# esp-rgbw.net
KiCad netlist of a schematic drawn in EAGLE
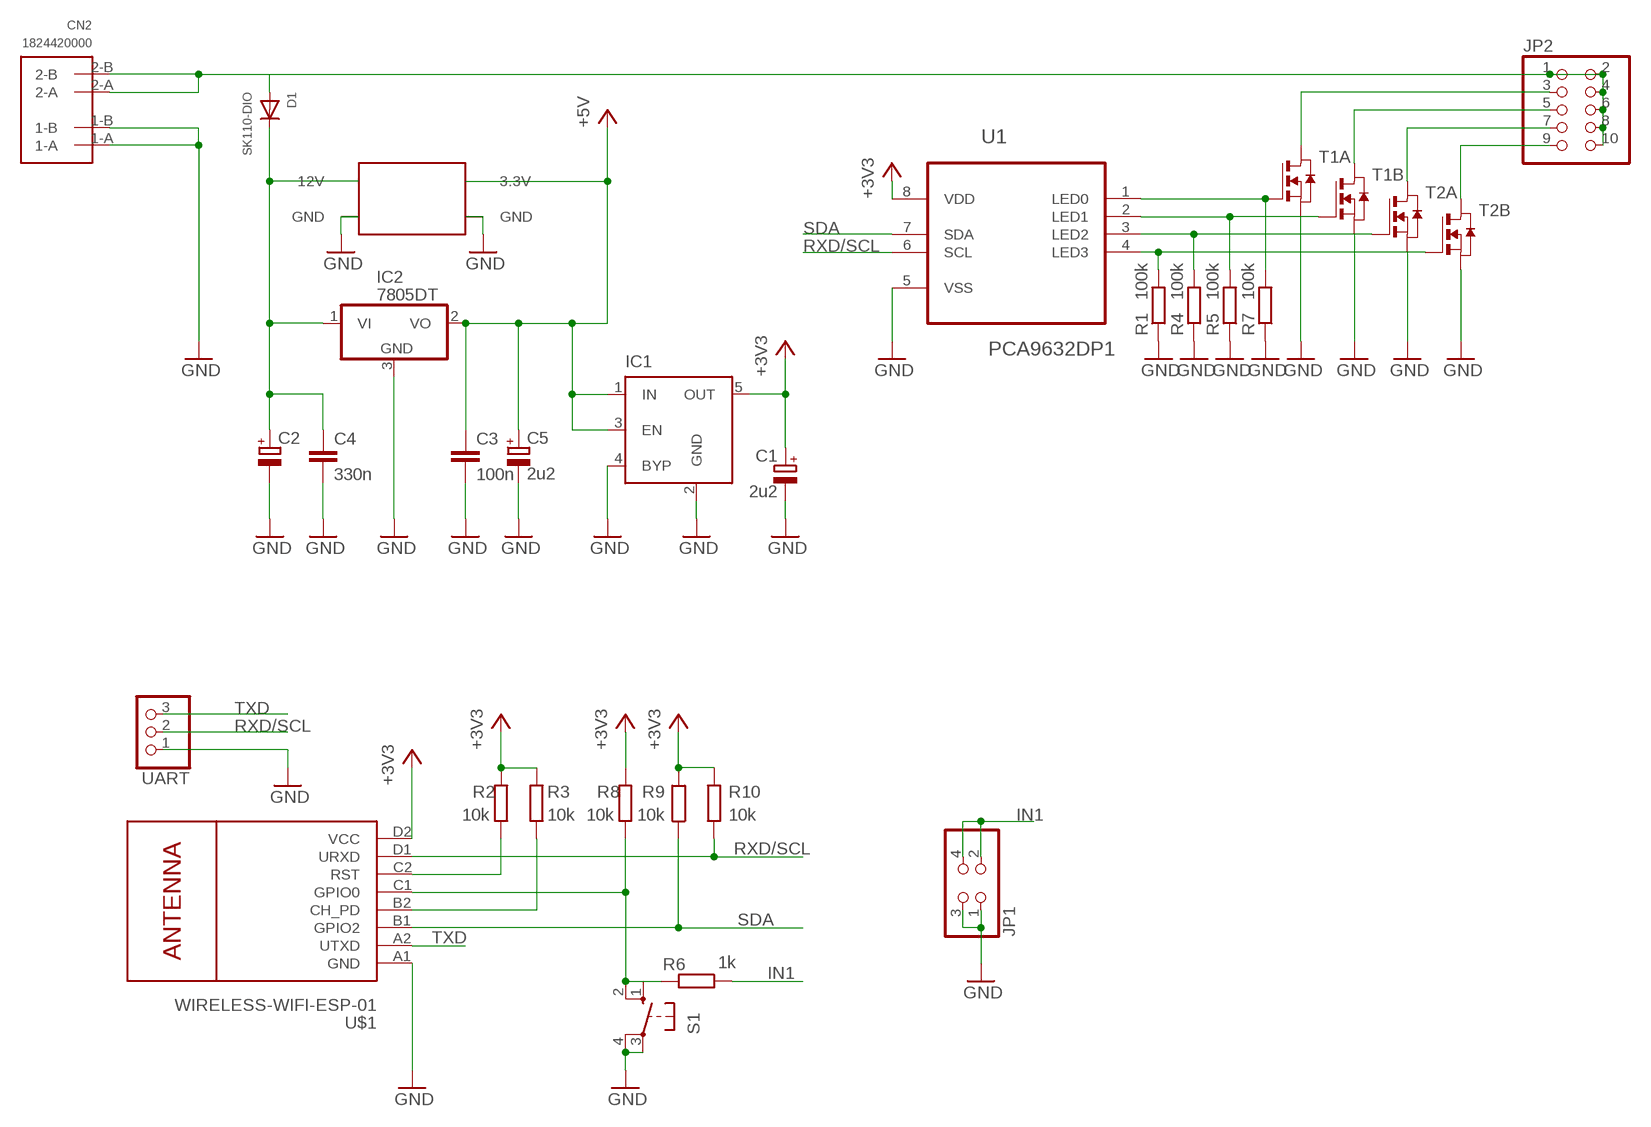
[diagram p0: schematic, sheet 1]

(export (version "E")
  (design (tool "Eeschema 10.0.6"))
  (components
    (comp (ref "C1")
      (value "2u2")
      (footprint "eagle-import:SMC_B")
      (libsource (lib "eagle-import") (part "CPOL-EUSMCB"))
    )
    (comp (ref "C2")
      (value "CPOL-EUC/6032-28R")
      (footprint "eagle-import:C_6032-28R")
      (libsource (lib "eagle-import") (part "CPOL-EUC/6032-28R"))
    )
    (comp (ref "C3")
      (value "100n")
      (footprint "eagle-import:C0805")
      (libsource (lib "eagle-import") (part "C-EUC0805"))
    )
    (comp (ref "C4")
      (value "330n")
      (footprint "eagle-import:C0805")
      (libsource (lib "eagle-import") (part "C-EUC0805"))
    )
    (comp (ref "C5")
      (value "2u2")
      (footprint "eagle-import:SMC_B")
      (libsource (lib "eagle-import") (part "CPOL-EUSMCB"))
    )
    (comp (ref "CN2")
      (value "1824420000")
      (footprint "eagle-import:1824420000")
      (fields (field (name "MF") "Weidmuller"))
      (libsource (lib "eagle-import") (part "1824420000"))
    )
    (comp (ref "D1")
      (value "SK110-DIO")
      (footprint "eagle-import:SMADIODE")
      (libsource (lib "eagle-import") (part "DIODESMA"))
    )
    (comp (ref "IC1")
      (value "MIC5219XX")
      (footprint "eagle-import:SOT23-5")
      (libsource (lib "eagle-import") (part "MIC5219XX"))
    )
    (comp (ref "IC2")
      (value "7805DT")
      (footprint "eagle-import:TO252")
      (libsource (lib "eagle-import") (part "78DT05"))
    )
    (comp (ref "JP1")
      (value "PINHD-2X2")
      (footprint "eagle-import:2X02")
      (libsource (lib "eagle-import") (part "PINHD-2X2"))
    )
    (comp (ref "JP2")
      (value "PINHD-2X5")
      (footprint "eagle-import:2X05")
      (libsource (lib "eagle-import") (part "PINHD-2X5"))
    )
    (comp (ref "R1")
      (value "100k")
      (footprint "eagle-import:R0805")
      (libsource (lib "eagle-import") (part "R-EU_R0805"))
    )
    (comp (ref "R2")
      (value "10k")
      (footprint "eagle-import:R0805")
      (libsource (lib "eagle-import") (part "R-EU_R0805"))
    )
    (comp (ref "R3")
      (value "10k")
      (footprint "eagle-import:R0805")
      (libsource (lib "eagle-import") (part "R-EU_R0805"))
    )
    (comp (ref "R4")
      (value "100k")
      (footprint "eagle-import:R0805")
      (libsource (lib "eagle-import") (part "R-EU_R0805"))
    )
    (comp (ref "R5")
      (value "100k")
      (footprint "eagle-import:R0805")
      (libsource (lib "eagle-import") (part "R-EU_R0805"))
    )
    (comp (ref "R6")
      (value "1k")
      (footprint "eagle-import:R0805")
      (libsource (lib "eagle-import") (part "R-EU_R0805"))
    )
    (comp (ref "R7")
      (value "100k")
      (footprint "eagle-import:R0805")
      (libsource (lib "eagle-import") (part "R-EU_R0805"))
    )
    (comp (ref "R8")
      (value "10k")
      (footprint "eagle-import:R0805")
      (libsource (lib "eagle-import") (part "R-EU_R0805"))
    )
    (comp (ref "R9")
      (value "10k")
      (footprint "eagle-import:R0805")
      (libsource (lib "eagle-import") (part "R-EU_R0805"))
    )
    (comp (ref "R10")
      (value "10k")
      (footprint "eagle-import:R0805")
      (libsource (lib "eagle-import") (part "R-EU_R0805"))
    )
    (comp (ref "S1")
      (value "10-XX")
      (footprint "eagle-import:B3F-10XX")
      (fields (field (name "MPN") "B3F-1000"))
      (libsource (lib "eagle-import") (part "10-XX"))
    )
    (comp (ref "T1")
      (value "NMOS2SO8")
      (footprint "eagle-import:SO8")
      (libsource (lib "eagle-import") (part "NMOS2SO8"))
    )
    (comp (ref "T2")
      (value "NMOS2SO8")
      (footprint "eagle-import:SO8")
      (libsource (lib "eagle-import") (part "NMOS2SO8"))
    )
    (comp (ref "U$1")
      (value "WIRELESS-WIFI-ESP-01")
      (footprint "eagle-import:WIRELESS-WIFI-ESP-01")
      (libsource (lib "eagle-import") (part "WIRELESS-WIFI-ESP-01"))
    )
    (comp (ref "U$2")
      (value "MP2307-MINI-360")
      (footprint "eagle-import:MP2307-MINI-360")
      (libsource (lib "eagle-import") (part "MP2307-MINI-360"))
    )
    (comp (ref "U1")
      (value "PCA9632DP1")
      (footprint "eagle-import:SOP65P490X110-8N")
      (libsource (lib "eagle-import") (part "PCA9632DP1"))
    )
    (comp (ref "UART")
      (value "PINHD-1X3")
      (footprint "eagle-import:1X03")
      (libsource (lib "eagle-import") (part "PINHD-1X3"))
    )
  )
  (nets
    (net (code "1") (name "+3V3") (class "Default")
      (node (ref "C1") (pin "+") (pinfunction "+_+") (pintype "passive"))
      (node (ref "IC1") (pin "5") (pinfunction "OUT_5") (pintype "output"))
      (node (ref "R10") (pin "2") (pinfunction "2_2") (pintype "passive"))
      (node (ref "R2") (pin "2") (pinfunction "2_2") (pintype "passive"))
      (node (ref "R3") (pin "2") (pinfunction "2_2") (pintype "passive"))
      (node (ref "R8") (pin "2") (pinfunction "2_2") (pintype "passive"))
      (node (ref "R9") (pin "2") (pinfunction "2_2") (pintype "passive"))
      (node (ref "U$1") (pin "D2") (pinfunction "VCC_D2") (pintype "power_in"))
      (node (ref "U1") (pin "8") (pinfunction "VDD_8") (pintype "power_in"))
    )
    (net (code "2") (name "+5V") (class "Default")
      (node (ref "C3") (pin "1") (pinfunction "1_1") (pintype "passive"))
      (node (ref "C5") (pin "+") (pinfunction "+_+") (pintype "passive"))
      (node (ref "IC1") (pin "1") (pinfunction "IN_1") (pintype "input"))
      (node (ref "IC1") (pin "3") (pinfunction "EN_3") (pintype "input"))
      (node (ref "IC2") (pin "2") (pinfunction "VO_2") (pintype "passive"))
      (node (ref "U$2") (pin "3.3V") (pinfunction "3.3V_3.3V") (pintype "power_in"))
    )
    (net (code "3") (name "/IN1") (class "Default")
      (node (ref "JP1") (pin "2") (pinfunction "2_2") (pintype "passive"))
      (node (ref "JP1") (pin "4") (pinfunction "4_4") (pintype "passive"))
      (node (ref "R6") (pin "1") (pinfunction "1_1") (pintype "passive"))
    )
    (net (code "4") (name "/RXD{slash}SCL") (class "Default")
      (node (ref "R10") (pin "1") (pinfunction "1_1") (pintype "passive"))
      (node (ref "U$1") (pin "D1") (pinfunction "URXD_D1") (pintype "bidirectional"))
      (node (ref "U1") (pin "6") (pinfunction "SCL_6") (pintype "input"))
      (node (ref "UART") (pin "2") (pinfunction "2_2") (pintype "passive"))
    )
    (net (code "5") (name "/SDA") (class "Default")
      (node (ref "R9") (pin "1") (pinfunction "1_1") (pintype "passive"))
      (node (ref "U$1") (pin "B1") (pinfunction "GPIO2_B1") (pintype "bidirectional"))
      (node (ref "U1") (pin "7") (pinfunction "SDA_7") (pintype "bidirectional"))
    )
    (net (code "6") (name "/TXD") (class "Default")
      (node (ref "U$1") (pin "A2") (pinfunction "UTXD_A2") (pintype "bidirectional"))
      (node (ref "UART") (pin "3") (pinfunction "3_3") (pintype "passive"))
    )
    (net (code "7") (name "GND") (class "Default")
      (node (ref "C1") (pin "-") (pinfunction "-_-") (pintype "passive"))
      (node (ref "C2") (pin "-") (pinfunction "-_-") (pintype "passive"))
      (node (ref "C3") (pin "2") (pinfunction "2_2") (pintype "passive"))
      (node (ref "C4") (pin "2") (pinfunction "2_2") (pintype "passive"))
      (node (ref "C5") (pin "-") (pinfunction "-_-") (pintype "passive"))
      (node (ref "CN2") (pin "1-A") (pinfunction "1-A_1-A") (pintype "bidirectional"))
      (node (ref "CN2") (pin "1-B") (pinfunction "1-B_1-B") (pintype "bidirectional"))
      (node (ref "IC1") (pin "2") (pinfunction "GND_2") (pintype "power_in"))
      (node (ref "IC1") (pin "4") (pinfunction "BYP_4") (pintype "passive"))
      (node (ref "IC2") (pin "3") (pinfunction "GND_3") (pintype "passive"))
      (node (ref "JP1") (pin "1") (pinfunction "1_1") (pintype "passive"))
      (node (ref "JP1") (pin "3") (pinfunction "3_3") (pintype "passive"))
      (node (ref "R1") (pin "1") (pinfunction "1_1") (pintype "passive"))
      (node (ref "R4") (pin "1") (pinfunction "1_1") (pintype "passive"))
      (node (ref "R5") (pin "1") (pinfunction "1_1") (pintype "passive"))
      (node (ref "R7") (pin "1") (pinfunction "1_1") (pintype "passive"))
      (node (ref "S1") (pin "3") (pinfunction "P_3") (pintype "passive"))
      (node (ref "S1") (pin "4") (pinfunction "P1_4") (pintype "passive"))
      (node (ref "T1") (pin "1") (pinfunction "S_1") (pintype "passive"))
      (node (ref "T1") (pin "3") (pinfunction "S_3") (pintype "passive"))
      (node (ref "T2") (pin "1") (pinfunction "S_1") (pintype "passive"))
      (node (ref "T2") (pin "3") (pinfunction "S_3") (pintype "passive"))
      (node (ref "U$1") (pin "A1") (pinfunction "GND_A1") (pintype "power_in"))
      (node (ref "U$2") (pin "GND@1") (pinfunction "GND_GND@1") (pintype "power_in"))
      (node (ref "U$2") (pin "GND@2") (pinfunction "GND_GND@2") (pintype "power_in"))
      (node (ref "U1") (pin "5") (pinfunction "VSS_5") (pintype "passive"))
      (node (ref "UART") (pin "1") (pinfunction "1_1") (pintype "passive"))
    )
    (net (code "8") (name "Net-(CN2-Pad2-A)") (class "Default")
      (node (ref "CN2") (pin "2-A") (pinfunction "2-A_2-A") (pintype "bidirectional"))
      (node (ref "CN2") (pin "2-B") (pinfunction "2-B_2-B") (pintype "bidirectional"))
      (node (ref "D1") (pin "A") (pinfunction "A_A") (pintype "passive"))
      (node (ref "JP2") (pin "1") (pinfunction "1_1") (pintype "passive"))
      (node (ref "JP2") (pin "10") (pinfunction "10_10") (pintype "passive"))
      (node (ref "JP2") (pin "2") (pinfunction "2_2") (pintype "passive"))
      (node (ref "JP2") (pin "4") (pinfunction "4_4") (pintype "passive"))
      (node (ref "JP2") (pin "6") (pinfunction "6_6") (pintype "passive"))
      (node (ref "JP2") (pin "8") (pinfunction "8_8") (pintype "passive"))
    )
    (net (code "9") (name "Net-(IC2-VI)") (class "Default")
      (node (ref "C2") (pin "+") (pinfunction "+_+") (pintype "passive"))
      (node (ref "C4") (pin "1") (pinfunction "1_1") (pintype "passive"))
      (node (ref "D1") (pin "C") (pinfunction "C_C") (pintype "passive"))
      (node (ref "IC2") (pin "1") (pinfunction "VI_1") (pintype "input"))
      (node (ref "U$2") (pin "12V") (pinfunction "12V_12V") (pintype "power_in"))
    )
    (net (code "10") (name "Net-(JP2-Pad3)") (class "Default")
      (node (ref "JP2") (pin "3") (pinfunction "3_3") (pintype "passive"))
      (node (ref "T1") (pin "7") (pinfunction "D_7") (pintype "passive"))
      (node (ref "T1") (pin "8") (pinfunction "D_8") (pintype "passive"))
    )
    (net (code "11") (name "Net-(JP2-Pad5)") (class "Default")
      (node (ref "JP2") (pin "5") (pinfunction "5_5") (pintype "passive"))
      (node (ref "T1") (pin "5") (pinfunction "D_5") (pintype "passive"))
      (node (ref "T1") (pin "6") (pinfunction "D_6") (pintype "passive"))
    )
    (net (code "12") (name "Net-(JP2-Pad7)") (class "Default")
      (node (ref "JP2") (pin "7") (pinfunction "7_7") (pintype "passive"))
      (node (ref "T2") (pin "7") (pinfunction "D_7") (pintype "passive"))
      (node (ref "T2") (pin "8") (pinfunction "D_8") (pintype "passive"))
    )
    (net (code "13") (name "Net-(JP2-Pad9)") (class "Default")
      (node (ref "JP2") (pin "9") (pinfunction "9_9") (pintype "passive"))
      (node (ref "T2") (pin "5") (pinfunction "D_5") (pintype "passive"))
      (node (ref "T2") (pin "6") (pinfunction "D_6") (pintype "passive"))
    )
    (net (code "14") (name "Net-(S1-S)") (class "Default")
      (node (ref "R6") (pin "2") (pinfunction "2_2") (pintype "passive"))
      (node (ref "R8") (pin "1") (pinfunction "1_1") (pintype "passive"))
      (node (ref "S1") (pin "1") (pinfunction "S_1") (pintype "passive"))
      (node (ref "S1") (pin "2") (pinfunction "S1_2") (pintype "passive"))
      (node (ref "U$1") (pin "C1") (pinfunction "GPIO0_C1") (pintype "bidirectional"))
    )
    (net (code "15") (name "Net-(T1A-G)") (class "Default")
      (node (ref "R7") (pin "2") (pinfunction "2_2") (pintype "passive"))
      (node (ref "T1") (pin "2") (pinfunction "G_2") (pintype "passive"))
      (node (ref "U1") (pin "1") (pinfunction "LED0_1") (pintype "output"))
    )
    (net (code "16") (name "Net-(T1B-G)") (class "Default")
      (node (ref "R5") (pin "2") (pinfunction "2_2") (pintype "passive"))
      (node (ref "T1") (pin "4") (pinfunction "G_4") (pintype "passive"))
      (node (ref "U1") (pin "2") (pinfunction "LED1_2") (pintype "output"))
    )
    (net (code "17") (name "Net-(T2A-G)") (class "Default")
      (node (ref "R4") (pin "2") (pinfunction "2_2") (pintype "passive"))
      (node (ref "T2") (pin "2") (pinfunction "G_2") (pintype "passive"))
      (node (ref "U1") (pin "3") (pinfunction "LED2_3") (pintype "output"))
    )
    (net (code "18") (name "Net-(T2B-G)") (class "Default")
      (node (ref "R1") (pin "2") (pinfunction "2_2") (pintype "passive"))
      (node (ref "T2") (pin "4") (pinfunction "G_4") (pintype "passive"))
      (node (ref "U1") (pin "4") (pinfunction "LED3_4") (pintype "output"))
    )
    (net (code "19") (name "Net-(U$1-CH_PD)") (class "Default")
      (node (ref "R3") (pin "1") (pinfunction "1_1") (pintype "passive"))
      (node (ref "U$1") (pin "B2") (pinfunction "CH_PD_B2") (pintype "bidirectional"))
    )
    (net (code "20") (name "Net-(U$1-RST)") (class "Default")
      (node (ref "R2") (pin "1") (pinfunction "1_1") (pintype "passive"))
      (node (ref "U$1") (pin "C2") (pinfunction "RST_C2") (pintype "bidirectional"))
    )
  )
)
